# W25N01GVZ.net
KiCad netlist of a schematic drawn in EAGLE
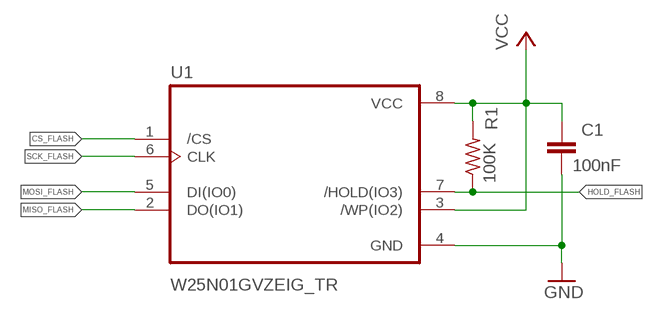
[diagram p0: schematic, sheet 1]

(export (version "E")
  (design (tool "Eeschema 10.0.6"))
  (components
    (comp (ref "C1")
      (value "100nF")
      (footprint "eagle-import:C0603")
      (libsource (lib "eagle-import") (part "C-EUC0603"))
    )
    (comp (ref "R1")
      (value "100K")
      (footprint "eagle-import:R0603")
      (libsource (lib "eagle-import") (part "R-US_R0603"))
    )
    (comp (ref "U1")
      (value "W25N01GVZEIG_TR")
      (footprint "eagle-import:SON127P800X600X80-9N")
      (fields (field (name "MF") "Winbond Electronics") (field (name "MP") "W25N01GVZEIG TR"))
      (libsource (lib "eagle-import") (part "W25N01GVZEIG_TR"))
    )
  )
  (nets
    (net (code "1") (name "CS_FLASH") (class "Default")
      (node (ref "U1") (pin "1") (pinfunction "/CS_1") (pintype "input"))
    )
    (net (code "2") (name "GND") (class "Default")
      (node (ref "C1") (pin "2") (pinfunction "2_2") (pintype "passive"))
      (node (ref "U1") (pin "4") (pinfunction "GND_4") (pintype "power_in"))
    )
    (net (code "3") (name "HOLD_FLASH") (class "Default")
      (node (ref "R1") (pin "1") (pinfunction "1_1") (pintype "passive"))
      (node (ref "U1") (pin "7") (pinfunction "/HOLD(IO3)_7") (pintype "bidirectional"))
    )
    (net (code "4") (name "MISO_FLASH") (class "Default")
      (node (ref "U1") (pin "2") (pinfunction "DO(IO1)_2") (pintype "bidirectional"))
    )
    (net (code "5") (name "MOSI_FLASH") (class "Default")
      (node (ref "U1") (pin "5") (pinfunction "DI(IO0)_5") (pintype "bidirectional"))
    )
    (net (code "6") (name "SCK_FLASH") (class "Default")
      (node (ref "U1") (pin "6") (pinfunction "CLK_6") (pintype "input"))
    )
    (net (code "7") (name "VCC") (class "Default")
      (node (ref "C1") (pin "1") (pinfunction "1_1") (pintype "passive"))
      (node (ref "R1") (pin "2") (pinfunction "2_2") (pintype "passive"))
      (node (ref "U1") (pin "3") (pinfunction "/WP(IO2)_3") (pintype "bidirectional"))
      (node (ref "U1") (pin "8") (pinfunction "VCC_8") (pintype "power_in"))
    )
  )
)
